# Interface.net
KiCad netlist of a schematic drawn in Altium Designer
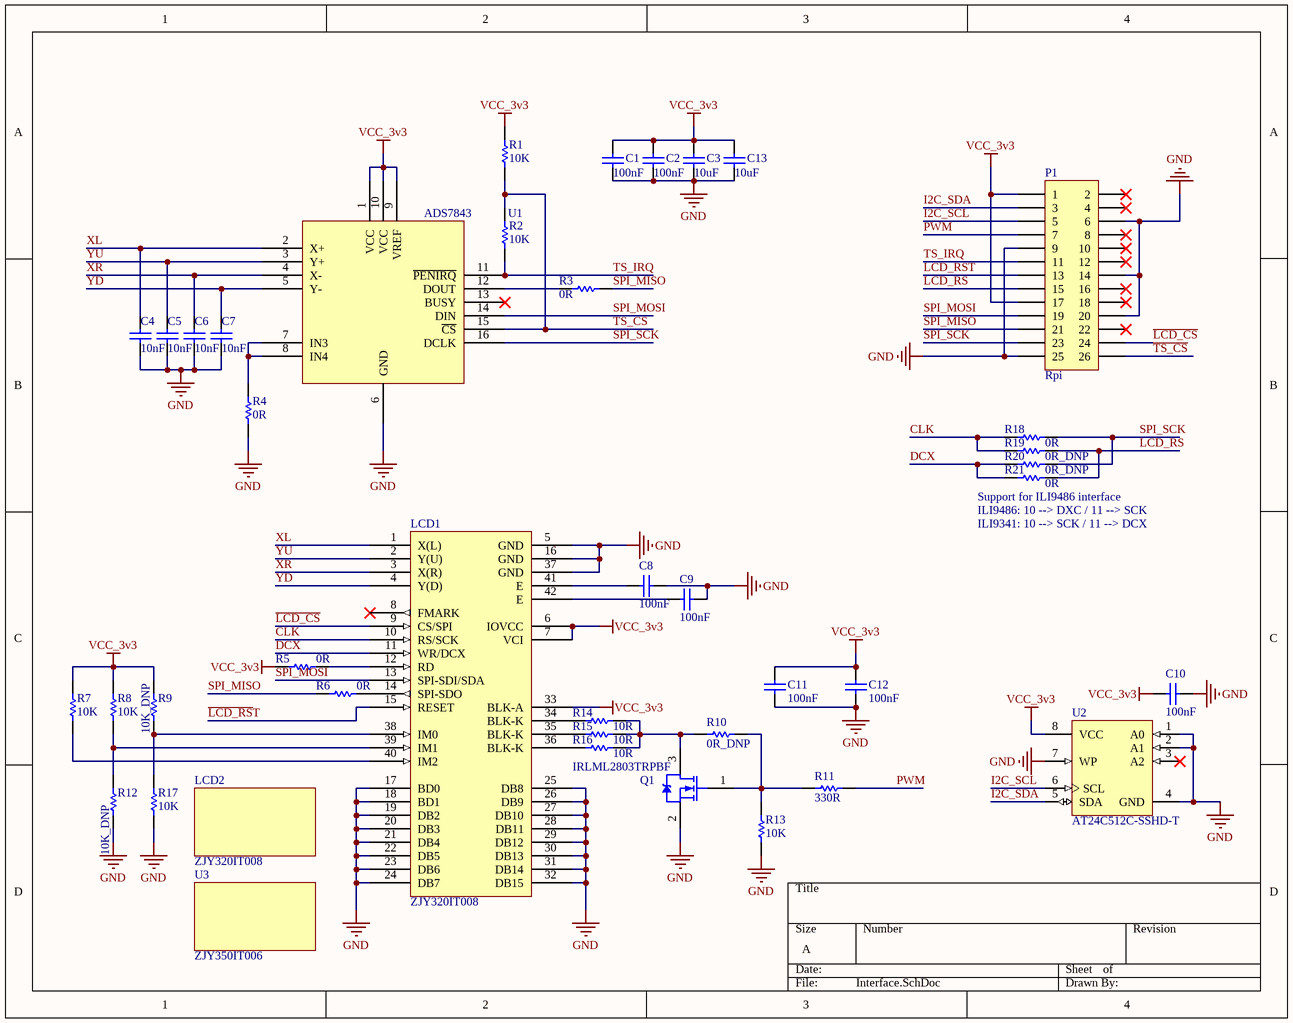
[diagram p0: Interface.SchDoc]

(export (version "E")
  (design (tool "Eeschema 10.0.6"))
  (components
    (comp (ref "C1")
      (value "100nF")
      (footprint "0603PKG")
      (description "Capacitor")
      (fields (field (name "Comment") "Cap") (field (name "PUBLISHER") "Altium Limited"))
      (libsource (lib "Miscellaneous Devices") (part "Cap"))
    )
    (comp (ref "C2")
      (value "100nF")
      (footprint "0603PKG")
      (description "Capacitor")
      (fields (field (name "Comment") "Cap") (field (name "PUBLISHER") "Altium Limited"))
      (libsource (lib "Miscellaneous Devices") (part "Cap"))
    )
    (comp (ref "C3")
      (value "10uF")
      (footprint "0603PKG")
      (description "Capacitor")
      (fields (field (name "Comment") "Cap") (field (name "PUBLISHER") "Altium Limited"))
      (libsource (lib "Miscellaneous Devices") (part "Cap"))
    )
    (comp (ref "C4")
      (value "10nF")
      (footprint "0603PKG")
      (description "Capacitor")
      (fields (field (name "Comment") "Cap") (field (name "PUBLISHER") "Altium Limited"))
      (libsource (lib "Miscellaneous Devices") (part "Cap"))
    )
    (comp (ref "C5")
      (value "10nF")
      (footprint "0603PKG")
      (description "Capacitor")
      (fields (field (name "Comment") "Cap") (field (name "PUBLISHER") "Altium Limited"))
      (libsource (lib "Miscellaneous Devices") (part "Cap"))
    )
    (comp (ref "C6")
      (value "10nF")
      (footprint "0603PKG")
      (description "Capacitor")
      (fields (field (name "Comment") "Cap") (field (name "PUBLISHER") "Altium Limited"))
      (libsource (lib "Miscellaneous Devices") (part "Cap"))
    )
    (comp (ref "C7")
      (value "10nF")
      (footprint "0603PKG")
      (description "Capacitor")
      (fields (field (name "Comment") "Cap") (field (name "PUBLISHER") "Altium Limited"))
      (libsource (lib "Miscellaneous Devices") (part "Cap"))
    )
    (comp (ref "C8")
      (value "100nF")
      (footprint "0603PKG")
      (description "Capacitor")
      (fields (field (name "Comment") "Cap") (field (name "PUBLISHER") "Altium Limited"))
      (libsource (lib "Miscellaneous Devices") (part "Cap"))
    )
    (comp (ref "C9")
      (value "100nF")
      (footprint "0603PKG")
      (description "Capacitor")
      (fields (field (name "Comment") "Cap") (field (name "PUBLISHER") "Altium Limited"))
      (libsource (lib "Miscellaneous Devices") (part "Cap"))
    )
    (comp (ref "C10")
      (value "100nF")
      (footprint "0603PKG")
      (description "Capacitor")
      (fields (field (name "Comment") "Cap") (field (name "PUBLISHER") "Altium Limited"))
      (libsource (lib "Miscellaneous Devices") (part "Cap"))
    )
    (comp (ref "C11")
      (value "100nF")
      (footprint "0603PKG")
      (description "Capacitor")
      (fields (field (name "Comment") "Cap") (field (name "PUBLISHER") "Altium Limited"))
      (libsource (lib "Miscellaneous Devices") (part "Cap"))
    )
    (comp (ref "C12")
      (value "100nF")
      (footprint "0603PKG")
      (description "Capacitor")
      (fields (field (name "Comment") "Cap") (field (name "PUBLISHER") "Altium Limited"))
      (libsource (lib "Miscellaneous Devices") (part "Cap"))
    )
    (comp (ref "C13")
      (value "10uF")
      (footprint "C0805")
      (description "Capacitor")
      (fields (field (name "Comment") "Cap") (field (name "PUBLISHER") "Altium Limited"))
      (libsource (lib "Miscellaneous Devices") (part "Cap"))
    )
    (comp (ref "LCD1")
      (value "ZJY320IT008")
      (footprint "FPC-40pin")
      (libsource (lib "Connector_IntLib") (part "ZJY320IT008-LIB"))
    )
    (comp (ref "LCD2")
      (value "ZJY320IT008")
      (footprint "ZJY320IT008")
      (libsource (lib "Connector_IntLib") (part "ZJY320IT008"))
    )
    (comp (ref "P1")
      (value "Rpi")
      (footprint "HDR2X13")
      (description "Header, 13-Pin, Dual row")
      (fields (field (name "PUBLISHER") "Altium Limited"))
      (libsource (lib "Miscellaneous Connectors") (part "Header 13X2"))
    )
    (comp (ref "Q1")
      (value "IRLML2803TRPBF")
      (footprint "SOT23")
      (description "N-Channel Power MOSFET")
      (fields (field (name "PUBLISHER") "Altium Limited"))
      (libsource (lib "Miscellaneous Devices") (part "NMOS-2"))
    )
    (comp (ref "R1")
      (value "10K")
      (footprint "0603PKG")
      (description "Resistor")
      (fields (field (name "Comment") "Res1") (field (name "PUBLISHER") "Altium Limited"))
      (libsource (lib "Miscellaneous Devices") (part "Res1"))
    )
    (comp (ref "R2")
      (value "10K")
      (footprint "0603PKG")
      (description "Resistor")
      (fields (field (name "Comment") "Res1") (field (name "PUBLISHER") "Altium Limited"))
      (libsource (lib "Miscellaneous Devices") (part "Res1"))
    )
    (comp (ref "R3")
      (value "0R")
      (footprint "0603PKG")
      (description "Resistor")
      (fields (field (name "Comment") "Res1") (field (name "PUBLISHER") "Altium Limited"))
      (libsource (lib "Miscellaneous Devices") (part "Res1"))
    )
    (comp (ref "R4")
      (value "0R")
      (footprint "0603PKG")
      (description "Resistor")
      (fields (field (name "Comment") "Res1") (field (name "PUBLISHER") "Altium Limited"))
      (libsource (lib "Miscellaneous Devices") (part "Res1"))
    )
    (comp (ref "R5")
      (value "0R")
      (footprint "0603PKG")
      (description "Resistor")
      (fields (field (name "Comment") "Res1") (field (name "PUBLISHER") "Altium Limited"))
      (libsource (lib "Miscellaneous Devices") (part "Res1"))
    )
    (comp (ref "R6")
      (value "0R")
      (footprint "0603PKG")
      (description "Resistor")
      (fields (field (name "Comment") "Res1") (field (name "PUBLISHER") "Altium Limited"))
      (libsource (lib "Miscellaneous Devices") (part "Res1"))
    )
    (comp (ref "R7")
      (value "10K")
      (footprint "0603PKG")
      (description "Resistor")
      (fields (field (name "Comment") "Res1") (field (name "PUBLISHER") "Altium Limited"))
      (libsource (lib "Miscellaneous Devices") (part "Res1"))
    )
    (comp (ref "R8")
      (value "10K")
      (footprint "0603PKG")
      (description "Resistor")
      (fields (field (name "Comment") "Res1") (field (name "PUBLISHER") "Altium Limited"))
      (libsource (lib "Miscellaneous Devices") (part "Res1"))
    )
    (comp (ref "R9")
      (value "10K_DNP")
      (footprint "0603PKG")
      (description "Resistor")
      (fields (field (name "Comment") "Res1") (field (name "PUBLISHER") "Altium Limited"))
      (libsource (lib "Miscellaneous Devices") (part "Res1"))
    )
    (comp (ref "R10")
      (value "0R_DNP")
      (footprint "0603PKG")
      (description "Resistor")
      (fields (field (name "Comment") "Res1") (field (name "PUBLISHER") "Altium Limited"))
      (libsource (lib "Miscellaneous Devices") (part "Res1"))
    )
    (comp (ref "R11")
      (value "330R")
      (footprint "0603PKG")
      (description "Resistor")
      (fields (field (name "Comment") "Res1") (field (name "PUBLISHER") "Altium Limited"))
      (libsource (lib "Miscellaneous Devices") (part "Res1"))
    )
    (comp (ref "R12")
      (value "10K_DNP")
      (footprint "0603PKG")
      (description "Resistor")
      (fields (field (name "Comment") "Res1") (field (name "PUBLISHER") "Altium Limited"))
      (libsource (lib "Miscellaneous Devices") (part "Res1"))
    )
    (comp (ref "R13")
      (value "10K")
      (footprint "0603PKG")
      (description "Resistor")
      (fields (field (name "Comment") "Res1") (field (name "PUBLISHER") "Altium Limited"))
      (libsource (lib "Miscellaneous Devices") (part "Res1"))
    )
    (comp (ref "R14")
      (value "10R")
      (footprint "0603PKG")
      (description "Resistor")
      (fields (field (name "Comment") "Res1") (field (name "PUBLISHER") "Altium Limited"))
      (libsource (lib "Miscellaneous Devices") (part "Res1"))
    )
    (comp (ref "R15")
      (value "10R")
      (footprint "0603PKG")
      (description "Resistor")
      (fields (field (name "Comment") "Res1") (field (name "PUBLISHER") "Altium Limited"))
      (libsource (lib "Miscellaneous Devices") (part "Res1"))
    )
    (comp (ref "R16")
      (value "10R")
      (footprint "0603PKG")
      (description "Resistor")
      (fields (field (name "Comment") "Res1") (field (name "PUBLISHER") "Altium Limited"))
      (libsource (lib "Miscellaneous Devices") (part "Res1"))
    )
    (comp (ref "R17")
      (value "10K")
      (footprint "0603PKG")
      (description "Resistor")
      (fields (field (name "Comment") "Res1") (field (name "PUBLISHER") "Altium Limited"))
      (libsource (lib "Miscellaneous Devices") (part "Res1"))
    )
    (comp (ref "R18")
      (value "0R")
      (footprint "0603PKG")
      (description "Resistor")
      (fields (field (name "Comment") "Res1") (field (name "PUBLISHER") "Altium Limited"))
      (libsource (lib "Miscellaneous Devices") (part "Res1"))
    )
    (comp (ref "R19")
      (value "0R_DNP")
      (footprint "0603PKG")
      (description "Resistor")
      (fields (field (name "Comment") "Res1") (field (name "PUBLISHER") "Altium Limited"))
      (libsource (lib "Miscellaneous Devices") (part "Res1"))
    )
    (comp (ref "R20")
      (value "0R_DNP")
      (footprint "0603PKG")
      (description "Resistor")
      (fields (field (name "Comment") "Res1") (field (name "PUBLISHER") "Altium Limited"))
      (libsource (lib "Miscellaneous Devices") (part "Res1"))
    )
    (comp (ref "R21")
      (value "0R")
      (footprint "0603PKG")
      (description "Resistor")
      (fields (field (name "Comment") "Res1") (field (name "PUBLISHER") "Altium Limited"))
      (libsource (lib "Miscellaneous Devices") (part "Res1"))
    )
    (comp (ref "U1") (value "ADS7843") (footprint "TSSOP16") (libsource (lib "Conn_Schlib") (part "ADS7843")))
    (comp (ref "U2")
      (value "AT24C512C-SSHD-T")
      (footprint "8S1_N")
      (description "1Kbit (128 x 8), 2-wire Bus Automotive Serial EEPROM with Write Protect, 2.5V, 8-Pin SOIC, Bulk")
      (libsource (lib "Atmel Serial EEPROM") (part "AT24C01BN-SP25-B"))
    )
    (comp (ref "U3")
      (value "ZJY350IT006")
      (footprint "ZJY350IT006")
      (libsource (lib "Connector_IntLib") (part "ZJY350IT006"))
    )
  )
  (nets
    (net (code "1") (name "/CLK") (class "Default")
      (node (ref "LCD1") (pin "10") (pinfunction "RS/SCK_10") (pintype "input"))
      (node (ref "R18") (pin "1") (pinfunction "1_1") (pintype "passive"))
      (node (ref "R19") (pin "1") (pinfunction "1_1") (pintype "passive"))
    )
    (net (code "2") (name "/DCX") (class "Default")
      (node (ref "LCD1") (pin "11") (pinfunction "WR/DCX_11") (pintype "input"))
      (node (ref "R20") (pin "1") (pinfunction "1_1") (pintype "passive"))
      (node (ref "R21") (pin "1") (pinfunction "1_1") (pintype "passive"))
    )
    (net (code "3") (name "/I2C_SCL") (class "Default")
      (node (ref "P1") (pin "5") (pinfunction "5_5") (pintype "passive"))
      (node (ref "U2") (pin "6") (pinfunction "SCL_6") (pintype "input"))
    )
    (net (code "4") (name "/I2C_SDA") (class "Default")
      (node (ref "P1") (pin "3") (pinfunction "3_3") (pintype "passive"))
      (node (ref "U2") (pin "5") (pinfunction "SDA_5") (pintype "bidirectional"))
    )
    (net (code "5") (name "/LCD_RS") (class "Default")
      (node (ref "P1") (pin "15") (pinfunction "15_15") (pintype "passive"))
      (node (ref "R19") (pin "2") (pinfunction "2_2") (pintype "passive"))
      (node (ref "R21") (pin "2") (pinfunction "2_2") (pintype "passive"))
    )
    (net (code "6") (name "/PWM") (class "Default")
      (node (ref "P1") (pin "7") (pinfunction "7_7") (pintype "passive"))
      (node (ref "R11") (pin "2") (pinfunction "2_2") (pintype "passive"))
    )
    (net (code "7") (name "/SPI_MISO") (class "Default")
      (node (ref "P1") (pin "21") (pinfunction "21_21") (pintype "passive"))
      (node (ref "R3") (pin "2") (pinfunction "2_2") (pintype "passive"))
      (node (ref "R6") (pin "1") (pinfunction "1_1") (pintype "passive"))
    )
    (net (code "8") (name "/SPI_MOSI") (class "Default")
      (node (ref "LCD1") (pin "13") (pinfunction "SPI-SDI/SDA_13") (pintype "input"))
      (node (ref "P1") (pin "19") (pinfunction "19_19") (pintype "passive"))
      (node (ref "U1") (pin "14") (pinfunction "DIN_14") (pintype "passive"))
    )
    (net (code "9") (name "/SPI_SCK") (class "Default")
      (node (ref "P1") (pin "23") (pinfunction "23_23") (pintype "passive"))
      (node (ref "R18") (pin "2") (pinfunction "2_2") (pintype "passive"))
      (node (ref "R20") (pin "2") (pinfunction "2_2") (pintype "passive"))
      (node (ref "U1") (pin "16") (pinfunction "DCLK_16") (pintype "passive"))
    )
    (net (code "10") (name "/TS_IRQ") (class "Default")
      (node (ref "P1") (pin "11") (pinfunction "11_11") (pintype "passive"))
      (node (ref "R2") (pin "2") (pinfunction "2_2") (pintype "passive"))
      (node (ref "U1") (pin "11") (pinfunction "~{PENIRQ}_11") (pintype "passive"))
    )
    (net (code "11") (name "/XL") (class "Default")
      (node (ref "C4") (pin "2") (pinfunction "2_2") (pintype "passive"))
      (node (ref "LCD1") (pin "1") (pinfunction "X(L)_1") (pintype "passive"))
      (node (ref "U1") (pin "2") (pinfunction "X+_2") (pintype "passive"))
    )
    (net (code "12") (name "/XR") (class "Default")
      (node (ref "C6") (pin "2") (pinfunction "2_2") (pintype "passive"))
      (node (ref "LCD1") (pin "3") (pinfunction "X(R)_3") (pintype "passive"))
      (node (ref "U1") (pin "4") (pinfunction "X-_4") (pintype "passive"))
    )
    (net (code "13") (name "/YD") (class "Default")
      (node (ref "C7") (pin "2") (pinfunction "2_2") (pintype "passive"))
      (node (ref "LCD1") (pin "4") (pinfunction "Y(D)_4") (pintype "passive"))
      (node (ref "U1") (pin "5") (pinfunction "Y-_5") (pintype "passive"))
    )
    (net (code "14") (name "/YU") (class "Default")
      (node (ref "C5") (pin "2") (pinfunction "2_2") (pintype "passive"))
      (node (ref "LCD1") (pin "2") (pinfunction "Y(U)_2") (pintype "passive"))
      (node (ref "U1") (pin "3") (pinfunction "Y+_3") (pintype "passive"))
    )
    (net (code "15") (name "/~{LCD_CS}") (class "Default")
      (node (ref "LCD1") (pin "9") (pinfunction "CS/SPI_9") (pintype "input"))
      (node (ref "P1") (pin "24") (pinfunction "24_24") (pintype "passive"))
    )
    (net (code "16") (name "/~{LCD_RS}T") (class "Default")
      (node (ref "LCD1") (pin "15") (pinfunction "RESET_15") (pintype "input"))
      (node (ref "P1") (pin "13") (pinfunction "13_13") (pintype "passive"))
    )
    (net (code "17") (name "/~{TS_CS}") (class "Default")
      (node (ref "P1") (pin "26") (pinfunction "26_26") (pintype "passive"))
      (node (ref "R1") (pin "2") (pinfunction "2_2") (pintype "passive"))
      (node (ref "R2") (pin "1") (pinfunction "1_1") (pintype "passive"))
      (node (ref "U1") (pin "15") (pinfunction "~{CS}_15") (pintype "passive"))
    )
    (net (code "18") (name "GND") (class "Default")
      (node (ref "C1") (pin "1") (pinfunction "1_1") (pintype "passive"))
      (node (ref "C10") (pin "1") (pinfunction "1_1") (pintype "passive"))
      (node (ref "C11") (pin "1") (pinfunction "1_1") (pintype "passive"))
      (node (ref "C12") (pin "2") (pinfunction "2_2") (pintype "passive"))
      (node (ref "C13") (pin "1") (pinfunction "1_1") (pintype "passive"))
      (node (ref "C2") (pin "1") (pinfunction "1_1") (pintype "passive"))
      (node (ref "C3") (pin "1") (pinfunction "1_1") (pintype "passive"))
      (node (ref "C4") (pin "1") (pinfunction "1_1") (pintype "passive"))
      (node (ref "C5") (pin "1") (pinfunction "1_1") (pintype "passive"))
      (node (ref "C6") (pin "1") (pinfunction "1_1") (pintype "passive"))
      (node (ref "C7") (pin "1") (pinfunction "1_1") (pintype "passive"))
      (node (ref "C8") (pin "1") (pinfunction "1_1") (pintype "passive"))
      (node (ref "C9") (pin "1") (pinfunction "1_1") (pintype "passive"))
      (node (ref "LCD1") (pin "16") (pinfunction "GND_16") (pintype "passive"))
      (node (ref "LCD1") (pin "17") (pinfunction "BD0_17") (pintype "passive"))
      (node (ref "LCD1") (pin "18") (pinfunction "BD1_18") (pintype "passive"))
      (node (ref "LCD1") (pin "19") (pinfunction "DB2_19") (pintype "passive"))
      (node (ref "LCD1") (pin "20") (pinfunction "DB3_20") (pintype "passive"))
      (node (ref "LCD1") (pin "21") (pinfunction "DB4_21") (pintype "passive"))
      (node (ref "LCD1") (pin "22") (pinfunction "DB5_22") (pintype "passive"))
      (node (ref "LCD1") (pin "23") (pinfunction "DB6_23") (pintype "passive"))
      (node (ref "LCD1") (pin "24") (pinfunction "DB7_24") (pintype "passive"))
      (node (ref "LCD1") (pin "25") (pinfunction "DB8_25") (pintype "passive"))
      (node (ref "LCD1") (pin "26") (pinfunction "DB9_26") (pintype "passive"))
      (node (ref "LCD1") (pin "27") (pinfunction "DB10_27") (pintype "passive"))
      (node (ref "LCD1") (pin "28") (pinfunction "DB11_28") (pintype "passive"))
      (node (ref "LCD1") (pin "29") (pinfunction "DB12_29") (pintype "passive"))
      (node (ref "LCD1") (pin "30") (pinfunction "DB13_30") (pintype "passive"))
      (node (ref "LCD1") (pin "31") (pinfunction "DB14_31") (pintype "passive"))
      (node (ref "LCD1") (pin "32") (pinfunction "DB15_32") (pintype "passive"))
      (node (ref "LCD1") (pin "37") (pinfunction "GND_37") (pintype "passive"))
      (node (ref "LCD1") (pin "5") (pinfunction "GND_5") (pintype "passive"))
      (node (ref "P1") (pin "14") (pinfunction "14_14") (pintype "passive"))
      (node (ref "P1") (pin "20") (pinfunction "20_20") (pintype "passive"))
      (node (ref "P1") (pin "25") (pinfunction "25_25") (pintype "passive"))
      (node (ref "P1") (pin "6") (pinfunction "6_6") (pintype "passive"))
      (node (ref "P1") (pin "9") (pinfunction "9_9") (pintype "passive"))
      (node (ref "Q1") (pin "2") (pinfunction "S_2") (pintype "passive"))
      (node (ref "R12") (pin "2") (pinfunction "2_2") (pintype "passive"))
      (node (ref "R13") (pin "1") (pinfunction "1_1") (pintype "passive"))
      (node (ref "R17") (pin "2") (pinfunction "2_2") (pintype "passive"))
      (node (ref "R4") (pin "1") (pinfunction "1_1") (pintype "passive"))
      (node (ref "U1") (pin "6") (pinfunction "GND_6") (pintype "passive"))
      (node (ref "U2") (pin "1") (pinfunction "A0_1") (pintype "input"))
      (node (ref "U2") (pin "2") (pinfunction "A1_2") (pintype "input"))
      (node (ref "U2") (pin "4") (pinfunction "GND_4") (pintype "power_in"))
      (node (ref "U2") (pin "7") (pinfunction "WP_7") (pintype "input"))
    )
    (net (code "19") (name "Net-(C8-Pad2)") (class "Default")
      (node (ref "C8") (pin "2") (pinfunction "2_2") (pintype "passive"))
      (node (ref "LCD1") (pin "41") (pinfunction "E_41") (pintype "passive"))
    )
    (net (code "20") (name "Net-(C9-Pad2)") (class "Default")
      (node (ref "C9") (pin "2") (pinfunction "2_2") (pintype "passive"))
      (node (ref "LCD1") (pin "42") (pinfunction "E_42") (pintype "passive"))
    )
    (net (code "21") (name "Net-(LCD1-BLK-K-Pad34)") (class "Default")
      (node (ref "LCD1") (pin "34") (pinfunction "BLK-K_34") (pintype "power_in"))
      (node (ref "R14") (pin "1") (pinfunction "1_1") (pintype "passive"))
    )
    (net (code "22") (name "Net-(LCD1-BLK-K-Pad35)") (class "Default")
      (node (ref "LCD1") (pin "35") (pinfunction "BLK-K_35") (pintype "power_in"))
      (node (ref "R15") (pin "1") (pinfunction "1_1") (pintype "passive"))
    )
    (net (code "23") (name "Net-(LCD1-BLK-K-Pad36)") (class "Default")
      (node (ref "LCD1") (pin "36") (pinfunction "BLK-K_36") (pintype "power_in"))
      (node (ref "R16") (pin "1") (pinfunction "1_1") (pintype "passive"))
    )
    (net (code "24") (name "Net-(LCD1-IM0)") (class "Default")
      (node (ref "LCD1") (pin "38") (pinfunction "IM0_38") (pintype "input"))
      (node (ref "R17") (pin "1") (pinfunction "1_1") (pintype "passive"))
      (node (ref "R9") (pin "2") (pinfunction "2_2") (pintype "passive"))
    )
    (net (code "25") (name "Net-(LCD1-IM1)") (class "Default")
      (node (ref "LCD1") (pin "39") (pinfunction "IM1_39") (pintype "input"))
      (node (ref "R12") (pin "1") (pinfunction "1_1") (pintype "passive"))
      (node (ref "R8") (pin "2") (pinfunction "2_2") (pintype "passive"))
    )
    (net (code "26") (name "Net-(LCD1-IM2)") (class "Default")
      (node (ref "LCD1") (pin "40") (pinfunction "IM2_40") (pintype "input"))
      (node (ref "R7") (pin "2") (pinfunction "2_2") (pintype "passive"))
    )
    (net (code "27") (name "Net-(LCD1-RD)") (class "Default")
      (node (ref "LCD1") (pin "12") (pinfunction "RD_12") (pintype "input"))
      (node (ref "R5") (pin "2") (pinfunction "2_2") (pintype "passive"))
    )
    (net (code "28") (name "Net-(LCD1-SPI-SDO)") (class "Default")
      (node (ref "LCD1") (pin "14") (pinfunction "SPI-SDO_14") (pintype "output"))
      (node (ref "R6") (pin "2") (pinfunction "2_2") (pintype "passive"))
    )
    (net (code "29") (name "Net-(Q1-D)") (class "Default")
      (node (ref "Q1") (pin "3") (pinfunction "D_3") (pintype "passive"))
      (node (ref "R10") (pin "1") (pinfunction "1_1") (pintype "passive"))
      (node (ref "R14") (pin "2") (pinfunction "2_2") (pintype "passive"))
      (node (ref "R15") (pin "2") (pinfunction "2_2") (pintype "passive"))
      (node (ref "R16") (pin "2") (pinfunction "2_2") (pintype "passive"))
    )
    (net (code "30") (name "Net-(Q1-G)") (class "Default")
      (node (ref "Q1") (pin "1") (pinfunction "G_1") (pintype "passive"))
      (node (ref "R10") (pin "2") (pinfunction "2_2") (pintype "passive"))
      (node (ref "R11") (pin "1") (pinfunction "1_1") (pintype "passive"))
      (node (ref "R13") (pin "2") (pinfunction "2_2") (pintype "passive"))
    )
    (net (code "31") (name "Net-(U1-DOUT)") (class "Default")
      (node (ref "R3") (pin "1") (pinfunction "1_1") (pintype "passive"))
      (node (ref "U1") (pin "12") (pinfunction "DOUT_12") (pintype "passive"))
    )
    (net (code "32") (name "Net-(U1-IN3)") (class "Default")
      (node (ref "R4") (pin "2") (pinfunction "2_2") (pintype "passive"))
      (node (ref "U1") (pin "7") (pinfunction "IN3_7") (pintype "passive"))
      (node (ref "U1") (pin "8") (pinfunction "IN4_8") (pintype "passive"))
    )
    (net (code "33") (name "VCC_3v3") (class "Default")
      (node (ref "C1") (pin "2") (pinfunction "2_2") (pintype "passive"))
      (node (ref "C10") (pin "2") (pinfunction "2_2") (pintype "passive"))
      (node (ref "C11") (pin "2") (pinfunction "2_2") (pintype "passive"))
      (node (ref "C12") (pin "1") (pinfunction "1_1") (pintype "passive"))
      (node (ref "C13") (pin "2") (pinfunction "2_2") (pintype "passive"))
      (node (ref "C2") (pin "2") (pinfunction "2_2") (pintype "passive"))
      (node (ref "C3") (pin "2") (pinfunction "2_2") (pintype "passive"))
      (node (ref "LCD1") (pin "33") (pinfunction "BLK-A_33") (pintype "power_in"))
      (node (ref "LCD1") (pin "6") (pinfunction "IOVCC_6") (pintype "passive"))
      (node (ref "LCD1") (pin "7") (pinfunction "VCI_7") (pintype "passive"))
      (node (ref "P1") (pin "1") (pinfunction "1_1") (pintype "passive"))
      (node (ref "P1") (pin "17") (pinfunction "17_17") (pintype "passive"))
      (node (ref "R1") (pin "1") (pinfunction "1_1") (pintype "passive"))
      (node (ref "R5") (pin "1") (pinfunction "1_1") (pintype "passive"))
      (node (ref "R7") (pin "1") (pinfunction "1_1") (pintype "passive"))
      (node (ref "R8") (pin "1") (pinfunction "1_1") (pintype "passive"))
      (node (ref "R9") (pin "1") (pinfunction "1_1") (pintype "passive"))
      (node (ref "U1") (pin "1") (pinfunction "VCC_1") (pintype "power_in"))
      (node (ref "U1") (pin "10") (pinfunction "VCC_10") (pintype "passive"))
      (node (ref "U1") (pin "9") (pinfunction "VREF_9") (pintype "passive"))
      (node (ref "U2") (pin "8") (pinfunction "VCC_8") (pintype "power_in"))
    )
    (net (code "34") (name "unconnected-(LCD1-FMARK-Pad8)") (class "Default")
      (node (ref "LCD1") (pin "8") (pinfunction "FMARK_8") (pintype "output+no_connect"))
    )
    (net (code "35") (name "unconnected-(P1-Pad2)") (class "Default")
      (node (ref "P1") (pin "2") (pinfunction "2_2") (pintype "passive+no_connect"))
    )
    (net (code "36") (name "unconnected-(P1-Pad4)") (class "Default")
      (node (ref "P1") (pin "4") (pinfunction "4_4") (pintype "passive+no_connect"))
    )
    (net (code "37") (name "unconnected-(P1-Pad8)") (class "Default")
      (node (ref "P1") (pin "8") (pinfunction "8_8") (pintype "passive+no_connect"))
    )
    (net (code "38") (name "unconnected-(P1-Pad10)") (class "Default")
      (node (ref "P1") (pin "10") (pinfunction "10_10") (pintype "passive+no_connect"))
    )
    (net (code "39") (name "unconnected-(P1-Pad12)") (class "Default")
      (node (ref "P1") (pin "12") (pinfunction "12_12") (pintype "passive+no_connect"))
    )
    (net (code "40") (name "unconnected-(P1-Pad16)") (class "Default")
      (node (ref "P1") (pin "16") (pinfunction "16_16") (pintype "passive+no_connect"))
    )
    (net (code "41") (name "unconnected-(P1-Pad18)") (class "Default")
      (node (ref "P1") (pin "18") (pinfunction "18_18") (pintype "passive+no_connect"))
    )
    (net (code "42") (name "unconnected-(P1-Pad22)") (class "Default")
      (node (ref "P1") (pin "22") (pinfunction "22_22") (pintype "passive+no_connect"))
    )
    (net (code "43") (name "unconnected-(U1-BUSY-Pad13)") (class "Default")
      (node (ref "U1") (pin "13") (pinfunction "BUSY_13") (pintype "passive+no_connect"))
    )
    (net (code "44") (name "unconnected-(U2-A2-Pad3)") (class "Default")
      (node (ref "U2") (pin "3") (pinfunction "A2_3") (pintype "input+no_connect"))
    )
  )
)
